# DC_DC_self_powerd.net
KiCad netlist of a schematic drawn in EAGLE
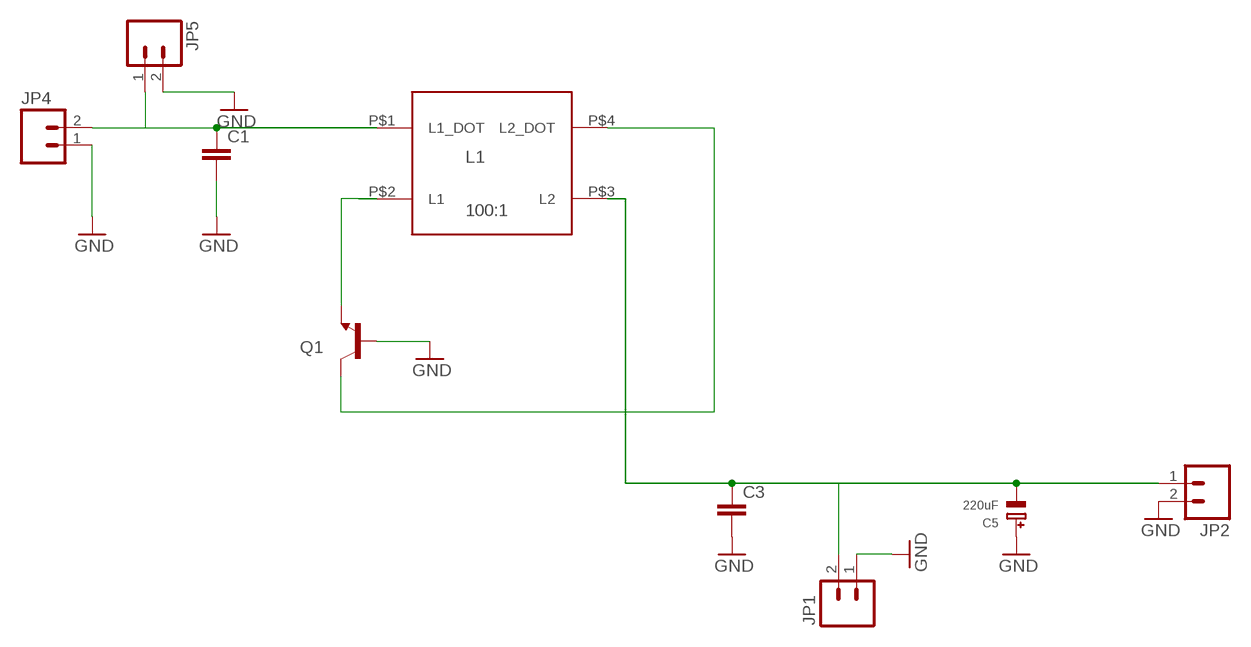
[diagram p0: schematic, sheet 1]

(export (version "E")
  (design (tool "Eeschema 10.0.6"))
  (components
    (comp (ref "C1")
      (value "CAP0805")
      (footprint "eagle-import:0805")
      (libsource (lib "eagle-import") (part "CAP0805"))
    )
    (comp (ref "C3")
      (value "CAP0805")
      (footprint "eagle-import:0805")
      (libsource (lib "eagle-import") (part "CAP0805"))
    )
    (comp (ref "C5")
      (value "220uF")
      (footprint "eagle-import:EIA7343-31_D-R")
      (libsource (lib "eagle-import") (part "CAP_TANTALUMD/7343_REFLOW"))
    )
    (comp (ref "JP1")
      (value "M02PTH")
      (footprint "eagle-import:1X02")
      (libsource (lib "eagle-import") (part "M02PTH"))
    )
    (comp (ref "JP2")
      (value "M02PTH")
      (footprint "eagle-import:1X02")
      (libsource (lib "eagle-import") (part "M02PTH"))
    )
    (comp (ref "JP4")
      (value "M02PTH")
      (footprint "eagle-import:1X02")
      (libsource (lib "eagle-import") (part "M02PTH"))
    )
    (comp (ref "JP5")
      (value "M02PTH")
      (footprint "eagle-import:1X02")
      (libsource (lib "eagle-import") (part "M02PTH"))
    )
    (comp (ref "L1")
      (value "100:1")
      (footprint "eagle-import:COILCRAFT_LPR6235")
      (libsource (lib "eagle-import") (part "COILCRAFT_LPR6235-752SML"))
    )
    (comp (ref "Q1")
      (value "TRANSISTOR_NPNSOT23-3")
      (footprint "eagle-import:SOT23-3")
      (libsource (lib "eagle-import") (part "TRANSISTOR_NPNSOT23-3"))
    )
  )
  (nets
    (net (code "1") (name "GND") (class "Default")
      (node (ref "C1") (pin "2") (pinfunction "2_2") (pintype "passive"))
      (node (ref "C3") (pin "2") (pinfunction "2_2") (pintype "passive"))
      (node (ref "C5") (pin "+") (pinfunction "+_+") (pintype "passive"))
      (node (ref "JP1") (pin "1") (pinfunction "1_1") (pintype "passive"))
      (node (ref "JP2") (pin "2") (pinfunction "2_2") (pintype "passive"))
      (node (ref "JP4") (pin "1") (pinfunction "1_1") (pintype "passive"))
      (node (ref "JP5") (pin "2") (pinfunction "2_2") (pintype "passive"))
      (node (ref "Q1") (pin "1") (pinfunction "B_1") (pintype "passive"))
    )
    (net (code "2") (name "Net-(L1-L1)") (class "Default")
      (node (ref "L1") (pin "P$2") (pinfunction "L1_P$2") (pintype "bidirectional"))
      (node (ref "Q1") (pin "2") (pinfunction "E_2") (pintype "passive"))
    )
    (net (code "3") (name "Net-(L1-L1_DOT)") (class "Default")
      (node (ref "C1") (pin "1") (pinfunction "1_1") (pintype "passive"))
      (node (ref "JP4") (pin "2") (pinfunction "2_2") (pintype "passive"))
      (node (ref "JP5") (pin "1") (pinfunction "1_1") (pintype "passive"))
      (node (ref "L1") (pin "P$1") (pinfunction "L1_DOT_P$1") (pintype "bidirectional"))
    )
    (net (code "4") (name "Net-(L1-L2)") (class "Default")
      (node (ref "C3") (pin "1") (pinfunction "1_1") (pintype "passive"))
      (node (ref "C5") (pin "-") (pinfunction "-_-") (pintype "passive"))
      (node (ref "JP1") (pin "2") (pinfunction "2_2") (pintype "passive"))
      (node (ref "JP2") (pin "1") (pinfunction "1_1") (pintype "passive"))
      (node (ref "L1") (pin "P$3") (pinfunction "L2_P$3") (pintype "bidirectional"))
    )
    (net (code "5") (name "Net-(L1-L2_DOT)") (class "Default")
      (node (ref "L1") (pin "P$4") (pinfunction "L2_DOT_P$4") (pintype "bidirectional"))
      (node (ref "Q1") (pin "3") (pinfunction "C_3") (pintype "passive"))
    )
  )
)
